# STM32_ESP.net
KiCad netlist of a schematic drawn in Altium Designer
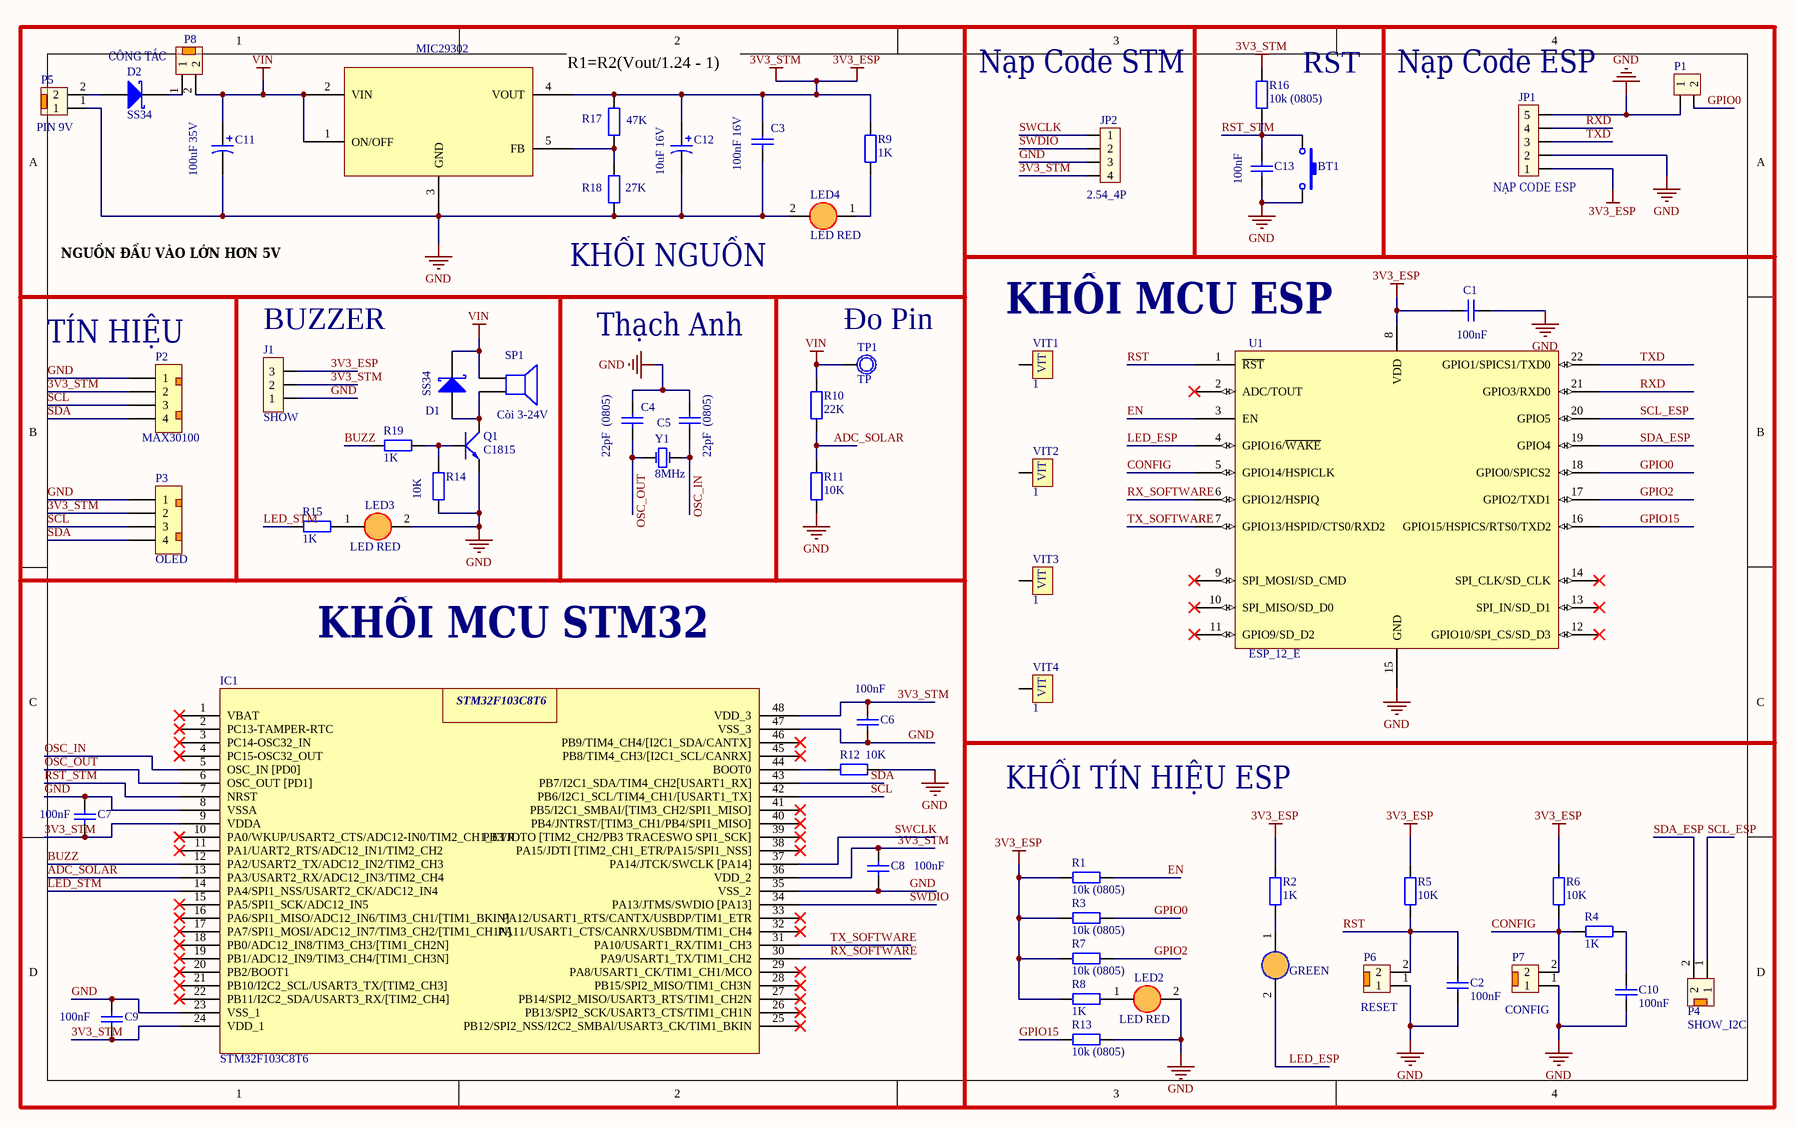
[diagram p0: STM32_ESP.SchDoc]

(export (version "E")
  (design (tool "Eeschema 10.0.6"))
  (components
    (comp (ref "BT1")
      (value "Nút Nhấn 2 Chân 3x6x2.5MM SMD")
      (footprint "Nut Nhan 2 Chan SMD_N")
      (description "Dán")
      (libsource (lib "SCH Chuan") (part "Nut Nhan 2 Chan SMD"))
    )
    (comp (ref "C1")
      (value "100nF")
      (footprint "Tu 0805")
      (description "Dán")
      (libsource (lib "NhomLib") (part "Tu 0805 106 16V 10%"))
    )
    (comp (ref "C2")
      (value "100nF")
      (footprint "tu 0805")
      (description "Dán")
      (libsource (lib "NhomLib") (part "Tu 0805 6.8nF 50V 10%"))
    )
    (comp (ref "C3")
      (value "100nF 16V")
      (footprint "tu 0805")
      (description "Dán")
      (libsource (lib "SCH Chuan") (part "Tu 0805 22pF 50V 10%"))
    )
    (comp (ref "C4")
      (value "22pF  (0805)")
      (footprint "tu 0805")
      (description "Dán")
      (libsource (lib "SCH Chuan") (part "Tu 0805 22pF 50V 10%"))
    )
    (comp (ref "C5")
      (value "22pF  (0805)")
      (footprint "tu 0805")
      (description "Dán")
      (libsource (lib "SCH Chuan") (part "Tu 0805 22pF 50V 10%"))
    )
    (comp (ref "C6")
      (value "100nF")
      (footprint "tu 0805")
      (description "Dán")
      (libsource (lib "SCH Chuan") (part "Tu 0805 104 50V 10%"))
    )
    (comp (ref "C7")
      (value "100nF")
      (footprint "tu 0805")
      (description "Dán")
      (libsource (lib "SCH Chuan") (part "Tu 0805 104 50V 10%"))
    )
    (comp (ref "C8")
      (value "100nF")
      (footprint "tu 0805")
      (description "Dán")
      (libsource (lib "SCH Chuan") (part "Tu 0805 104 50V 10%"))
    )
    (comp (ref "C9")
      (value "100nF")
      (footprint "tu 0805")
      (description "Dán")
      (libsource (lib "SCH Chuan") (part "Tu 0805 104 50V 10%"))
    )
    (comp (ref "C10")
      (value "100nF")
      (footprint "tu 0805")
      (description "Dán")
      (libsource (lib "NhomLib") (part "Tu 0805 6.8nF 50V 10%"))
    )
    (comp (ref "C11")
      (value "100uF 35V")
      (footprint "CAP_ALUM_SMD_100102_TYPE_G")
      (description "CAP ALUM 330uF 20% 35V SMD")
      (fields (field (name "MPN") "EEE-FK1C331P") (field (name "MFR") "Panasonic"))
      (libsource (lib "NhomLib") (part "EEE-FK1C331P"))
    )
    (comp (ref "C12")
      (value "10uF 16V")
      (footprint "CAP_ALUM_SMD_5054_TYPE_C")
      (description "CAP ALUM 33uF 20% 16V SMD")
      (fields (field (name "MPN") "EEE-FK1C330P") (field (name "MFR") "Panasonic"))
      (libsource (lib "NhomLib") (part "EEE-FK1C330P"))
    )
    (comp (ref "C13")
      (value "100nF")
      (footprint "tu 0805")
      (description "Dán")
      (libsource (lib "SCH Chuan") (part "Tu 0805 104 50V 10%"))
    )
    (comp (ref "D1")
      (value "SS34")
      (footprint "DIODE_DO214AC_SMA")
      (description "DIODE SCHOTTKY 40V 3A SMA")
      (libsource (lib "NhomLib") (part "SS34"))
    )
    (comp (ref "D2")
      (value "SS34")
      (footprint "DIODE_DO214AC_SMA")
      (description "DIODE SCHOTTKY 40V 3A SMA")
      (libsource (lib "NhomLib") (part "SS34"))
    )
    (comp (ref "IC1")
      (value "STM32F103C8T6")
      (footprint "LQFP48")
      (description "Dán")
      (libsource (lib "SCH Chuan") (part "STM32F103C8T6"))
    )
    (comp (ref "J1")
      (value "SHOW")
      (footprint "jump don duc thang 2.54_3p")
      (description "Cắm")
      (libsource (lib "NhomLib") (part "Jump Don Duc Thang 2.54_3P"))
    )
    (comp (ref "JP1")
      (value "NẠP CODE ESP")
      (footprint "jump don duc 2.54_5p")
      (description "Cắm")
      (libsource (lib "NhomLib") (part "Jump Don Duc 2.54_5P"))
    )
    (comp (ref "JP2")
      (value "2.54_4P")
      (footprint "JUMP DON DUC 2.54_4P")
      (description "Cắm")
      (libsource (lib "SCH Chuan") (part "Jump Don Duc 2.54_4P"))
    )
    (comp (ref "LED1")
      (value "GREEN")
      (footprint "led 0805")
      (description "Dán")
      (libsource (lib "NhomLib") (part "Led 0805 Xanh Duong"))
    )
    (comp (ref "LED2")
      (value "LED RED")
      (footprint "led 0805")
      (description "Dán")
      (libsource (lib "NhomLib") (part "Led 0805 Do"))
    )
    (comp (ref "LED3")
      (value "LED RED")
      (footprint "led 0805")
      (description "Dán")
      (libsource (lib "NhomLib") (part "Led 0805 Do"))
    )
    (comp (ref "LED4")
      (value "LED RED")
      (footprint "led 0805")
      (description "Dán")
      (libsource (lib "SCH Chuan") (part "Led 0805 Do"))
    )
    (comp (ref "MIC1")
      (value "MIC29302")
      (footprint "Mic5V")
      (description "3A")
      (libsource (lib "node_mcu") (part "Mic5V"))
    )
    (comp (ref "P1")
      (value "2P")
      (footprint "Jump don duc 2.54_2P")
      (description "Cắm")
      (libsource (lib "NhomLib") (part "Jum don duc 2.54_2P"))
    )
    (comp (ref "P2")
      (value "MAX30100")
      (footprint "Header Duc Thang 4p 2.54")
      (description "Cắm")
      (libsource (lib "NhomLib") (part "Header 2.54_4p Duc Thang"))
    )
    (comp (ref "P3")
      (value "OLED")
      (footprint "Header Duc Thang 4p 2.54")
      (description "Cắm")
      (libsource (lib "NhomLib") (part "Header 2.54_4p Duc Thang"))
    )
    (comp (ref "P4")
      (value "SHOW_I2C")
      (footprint "Header Duc Thang 2P 2.54")
      (description "Cắm")
      (libsource (lib "") (part "Header 2.54-2p Duc Thang_2"))
    )
    (comp (ref "P5")
      (value "PIN 9V")
      (footprint "Header Duc Thang 2P 2.54")
      (description "Cắm")
      (libsource (lib "NhomLib") (part "Header 2.54-2p Duc Thang"))
    )
    (comp (ref "P6")
      (value "RESET")
      (footprint "Header Duc Thang 2P 2.54")
      (description "Cắm")
      (libsource (lib "NhomLib") (part "Header 2.54-2p Duc Thang"))
    )
    (comp (ref "P7")
      (value "CONFIG")
      (footprint "Header Duc Thang 2P 2.54")
      (description "Cắm")
      (libsource (lib "NhomLib") (part "Header 2.54-2p Duc Thang"))
    )
    (comp (ref "P8")
      (value "CÔNG TẮC")
      (footprint "Header Duc Thang 2P 2.54")
      (description "Cắm")
      (libsource (lib "") (part "Header 2.54-2p Duc Thang_1"))
    )
    (comp (ref "Q1")
      (value "C1815")
      (footprint "SOT23B")
      (description "Dán")
      (libsource (lib "SCH Chuan") (part "C1815"))
    )
    (comp (ref "R1")
      (value "10k (0805)")
      (footprint "tro 0805")
      (description "Dán")
      (libsource (lib "NhomLib") (part "Tro 0805 5% 10k"))
    )
    (comp (ref "R2")
      (value "1K")
      (footprint "tro 0805")
      (description "Dán")
      (libsource (lib "NhomLib") (part "Tro 0805 5% 1.5k"))
    )
    (comp (ref "R3")
      (value "10k (0805)")
      (footprint "tro 0805")
      (description "Dán")
      (libsource (lib "NhomLib") (part "Tro 0805 5% 10k"))
    )
    (comp (ref "R4")
      (value "1K")
      (footprint "tro 0805")
      (description "Dán")
      (libsource (lib "NhomLib") (part "Tro 0805 5% 1.5k"))
    )
    (comp (ref "R5")
      (value "10K")
      (footprint "tro 0805")
      (description "Dán")
      (libsource (lib "NhomLib") (part "Tro 0805 5% 10k"))
    )
    (comp (ref "R6")
      (value "10K")
      (footprint "tro 0805")
      (description "Dán")
      (libsource (lib "NhomLib") (part "Tro 0805 5% 10k"))
    )
    (comp (ref "R7")
      (value "10k (0805)")
      (footprint "tro 0805")
      (description "Dán")
      (libsource (lib "NhomLib") (part "Tro 0805 5% 10k"))
    )
    (comp (ref "R8")
      (value "1K")
      (footprint "tro 0805")
      (description "Dán")
      (libsource (lib "NhomLib") (part "Tro 0805 5% 1.5k"))
    )
    (comp (ref "R9")
      (value "1K")
      (footprint "tro 0805")
      (description "Dán")
      (libsource (lib "NhomLib") (part "Tro 0805 5% 10k"))
    )
    (comp (ref "R10")
      (value "22K")
      (footprint "tro 0805")
      (description "Dán")
      (libsource (lib "SCH Chuan") (part "Tro 0805 5% 10k"))
    )
    (comp (ref "R11")
      (value "10K")
      (footprint "tro 0805")
      (description "Dán")
      (libsource (lib "SCH Chuan") (part "Tro 0805 5% 10k"))
    )
    (comp (ref "R12")
      (value "10K")
      (footprint "tro 0805")
      (description "Dán")
      (libsource (lib "SCH Chuan") (part "Tro 0805 1% 10k"))
    )
    (comp (ref "R13")
      (value "10k (0805)")
      (footprint "tro 0805")
      (description "Dán")
      (libsource (lib "NhomLib") (part "Tro 0805 5% 10k"))
    )
    (comp (ref "R14")
      (value "10K")
      (footprint "tro 0805")
      (description "Dán")
      (libsource (lib "SCH Chuan") (part "Tro 0805 5% 470R"))
    )
    (comp (ref "R15")
      (value "1K")
      (footprint "tro 0805")
      (description "Dán")
      (libsource (lib "NhomLib") (part "Tro 0805 5% 1.5k"))
    )
    (comp (ref "R16")
      (value "10k (0805)")
      (footprint "tro 0805")
      (description "Dán")
      (libsource (lib "SCH Chuan") (part "Tro 0805 5% 10k"))
    )
    (comp (ref "R17")
      (value "47K")
      (footprint "tro 0805")
      (description "Dán")
      (libsource (lib "NhomLib") (part "Tro 0805 5% 10k"))
    )
    (comp (ref "R18")
      (value "27K")
      (footprint "tro 0805")
      (description "Dán")
      (libsource (lib "NhomLib") (part "Tro 0805 5% 10k"))
    )
    (comp (ref "R19")
      (value "1K")
      (footprint "tro 0805")
      (description "Dán")
      (libsource (lib "SCH Chuan") (part "Tro 0805 5% 470R"))
    )
    (comp (ref "SP1")
      (value "Còi 3-24V")
      (footprint "SPEAKER")
      (description "Cắm")
      (libsource (lib "NhomLib") (part "Coi Chip 5V"))
    )
    (comp (ref "TP1")
      (value "TP")
      (footprint "TP1")
      (description "Test Point")
      (libsource (lib "NhomLib") (part "TP1"))
    )
    (comp (ref "U1")
      (value "ESP_12_E")
      (footprint "ESP8266_12_E_L")
      (description "ESP-12 Wi-Fi Module by AI-Thinker")
      (libsource (lib "Schlib1") (part "ESP_12_E"))
    )
    (comp (ref "VIT1")
      (value "1")
      (footprint "VIT")
      (description "Oc Vit")
      (libsource (lib "NhomLib") (part "VIT"))
    )
    (comp (ref "VIT2")
      (value "1")
      (footprint "VIT")
      (description "Oc Vit")
      (libsource (lib "NhomLib") (part "VIT"))
    )
    (comp (ref "VIT3")
      (value "1")
      (footprint "VIT")
      (description "Oc Vit")
      (libsource (lib "NhomLib") (part "VIT"))
    )
    (comp (ref "VIT4")
      (value "1")
      (footprint "VIT")
      (description "Oc Vit")
      (libsource (lib "NhomLib") (part "VIT"))
    )
    (comp (ref "Y1")
      (value "8MHz")
      (footprint "thach anh 49s smd")
      (description "Dán")
      (libsource (lib "SCH Chuan") (part "Thach anh 8MHz 49S SMD"))
    )
  )
  (nets
    (net (code "1") (name "/ADC_SOLAR") (class "Default")
      (node (ref "IC1") (pin "13") (pinfunction "PA3/USART2_RX/ADC12_IN3/TIM2_CH4_13") (pintype "passive"))
      (node (ref "R10") (pin "1") (pinfunction "1_1") (pintype "passive"))
      (node (ref "R11") (pin "2") (pinfunction "2_2") (pintype "passive"))
    )
    (net (code "2") (name "/BUZZ") (class "Default")
      (node (ref "IC1") (pin "12") (pinfunction "PA2/USART2_TX/ADC12_IN2/TIM2_CH3_12") (pintype "passive"))
      (node (ref "R19") (pin "2") (pinfunction "2_2") (pintype "passive"))
    )
    (net (code "3") (name "/CONFIG") (class "Default")
      (node (ref "P7") (pin "2") (pinfunction "2_2") (pintype "passive"))
      (node (ref "R4") (pin "1") (pinfunction "1_1") (pintype "passive"))
      (node (ref "R6") (pin "2") (pinfunction "2_2") (pintype "passive"))
      (node (ref "U1") (pin "5") (pinfunction "GPIO14/HSPICLK_5") (pintype "bidirectional"))
    )
    (net (code "4") (name "/EN") (class "Default")
      (node (ref "R1") (pin "1") (pinfunction "1_1") (pintype "passive"))
      (node (ref "U1") (pin "3") (pinfunction "EN_3") (pintype "passive"))
    )
    (net (code "5") (name "/GPIO0") (class "Default")
      (node (ref "P1") (pin "2") (pinfunction "2_2") (pintype "passive"))
      (node (ref "R3") (pin "1") (pinfunction "1_1") (pintype "passive"))
      (node (ref "U1") (pin "18") (pinfunction "GPIO0/SPICS2_18") (pintype "bidirectional"))
    )
    (net (code "6") (name "/GPIO2") (class "Default")
      (node (ref "R7") (pin "1") (pinfunction "1_1") (pintype "passive"))
      (node (ref "U1") (pin "17") (pinfunction "GPIO2/TXD1_17") (pintype "bidirectional"))
    )
    (net (code "7") (name "/GPIO15") (class "Default")
      (node (ref "R13") (pin "2") (pinfunction "2_2") (pintype "passive"))
      (node (ref "U1") (pin "16") (pinfunction "GPIO15/HSPICS/RTS0/TXD2_16") (pintype "bidirectional"))
    )
    (net (code "8") (name "/LED_ESP") (class "Default")
      (node (ref "LED1") (pin "2") (pinfunction "K_2") (pintype "passive"))
      (node (ref "U1") (pin "4") (pinfunction "GPIO16/~{WAKE}_4") (pintype "bidirectional"))
    )
    (net (code "9") (name "/LED_STM") (class "Default")
      (node (ref "IC1") (pin "14") (pinfunction "PA4/SPI1_NSS/USART2_CK/ADC12_IN4_14") (pintype "passive"))
      (node (ref "R15") (pin "1") (pinfunction "1_1") (pintype "passive"))
    )
    (net (code "10") (name "/OSC_IN") (class "Default")
      (node (ref "C5") (pin "2") (pinfunction "2_2") (pintype "passive"))
      (node (ref "IC1") (pin "5") (pinfunction "OSC_IN_[PD0]_5") (pintype "passive"))
      (node (ref "Y1") (pin "2") (pinfunction "OSC2_2") (pintype "passive"))
    )
    (net (code "11") (name "/OSC_OUT") (class "Default")
      (node (ref "C4") (pin "2") (pinfunction "2_2") (pintype "passive"))
      (node (ref "IC1") (pin "6") (pinfunction "OSC_OUT_[PD1]_6") (pintype "passive"))
      (node (ref "Y1") (pin "1") (pinfunction "OSC1_1") (pintype "passive"))
    )
    (net (code "12") (name "/RST") (class "Default")
      (node (ref "C2") (pin "1") (pinfunction "1_1") (pintype "passive"))
      (node (ref "P6") (pin "2") (pinfunction "2_2") (pintype "passive"))
      (node (ref "R5") (pin "2") (pinfunction "2_2") (pintype "passive"))
      (node (ref "U1") (pin "1") (pinfunction "~{RST}_1") (pintype "passive"))
    )
    (net (code "13") (name "/RST_STM") (class "Default")
      (node (ref "BT1") (pin "1") (pinfunction "1_1") (pintype "passive"))
      (node (ref "C13") (pin "1") (pinfunction "1_1") (pintype "passive"))
      (node (ref "IC1") (pin "7") (pinfunction "NRST_7") (pintype "passive"))
      (node (ref "R16") (pin "1") (pinfunction "1_1") (pintype "passive"))
    )
    (net (code "14") (name "/RXD") (class "Default")
      (node (ref "JP1") (pin "4") (pinfunction "4_4") (pintype "passive"))
      (node (ref "U1") (pin "21") (pinfunction "GPIO3/RXD0_21") (pintype "bidirectional"))
    )
    (net (code "15") (name "/RX_SOFTWARE") (class "Default")
      (node (ref "IC1") (pin "30") (pinfunction "PA9/USART1_TX/TIM1_CH2_30") (pintype "passive"))
      (node (ref "U1") (pin "6") (pinfunction "GPIO12/HSPIQ_6") (pintype "bidirectional"))
    )
    (net (code "16") (name "/SCL") (class "Default")
      (node (ref "IC1") (pin "42") (pinfunction "PB6/I2C1_SCL/TIM4_CH1/[USART1_TX]_42") (pintype "passive"))
      (node (ref "P2") (pin "3") (pinfunction "3_3") (pintype "passive"))
      (node (ref "P3") (pin "3") (pinfunction "3_3") (pintype "passive"))
    )
    (net (code "17") (name "/SCL_ESP") (class "Default")
      (node (ref "P4") (pin "1") (pinfunction "1_1") (pintype "passive"))
      (node (ref "U1") (pin "20") (pinfunction "GPIO5_20") (pintype "bidirectional"))
    )
    (net (code "18") (name "/SDA") (class "Default")
      (node (ref "IC1") (pin "43") (pinfunction "PB7/I2C1_SDA/TIM4_CH2[USART1_RX]_43") (pintype "passive"))
      (node (ref "P2") (pin "4") (pinfunction "4_4") (pintype "passive"))
      (node (ref "P3") (pin "4") (pinfunction "4_4") (pintype "passive"))
    )
    (net (code "19") (name "/SDA_ESP") (class "Default")
      (node (ref "P4") (pin "2") (pinfunction "2_2") (pintype "passive"))
      (node (ref "U1") (pin "19") (pinfunction "GPIO4_19") (pintype "bidirectional"))
    )
    (net (code "20") (name "/SWCLK") (class "Default")
      (node (ref "IC1") (pin "37") (pinfunction "PA14/JTCK/SWCLK_[PA14]_37") (pintype "passive"))
      (node (ref "JP2") (pin "1") (pinfunction "1_1") (pintype "passive"))
    )
    (net (code "21") (name "/SWDIO") (class "Default")
      (node (ref "IC1") (pin "34") (pinfunction "PA13/JTMS/SWDIO_[PA13]_34") (pintype "passive"))
      (node (ref "JP2") (pin "2") (pinfunction "2_2") (pintype "passive"))
    )
    (net (code "22") (name "/TXD") (class "Default")
      (node (ref "JP1") (pin "3") (pinfunction "3_3") (pintype "passive"))
      (node (ref "U1") (pin "22") (pinfunction "GPIO1/SPICS1/TXD0_22") (pintype "bidirectional"))
    )
    (net (code "23") (name "/TX_SOFTWARE") (class "Default")
      (node (ref "IC1") (pin "31") (pinfunction "PA10/USART1_RX/TIM1_CH3_31") (pintype "passive"))
      (node (ref "U1") (pin "7") (pinfunction "GPIO13/HSPID/CTS0/RXD2_7") (pintype "bidirectional"))
    )
    (net (code "24") (name "3V3_ESP") (class "Default")
      (node (ref "C1") (pin "2") (pinfunction "2_2") (pintype "passive"))
      (node (ref "C12") (pin "1") (pinfunction "1_1") (pintype "passive"))
      (node (ref "C3") (pin "1") (pinfunction "1_1") (pintype "passive"))
      (node (ref "C6") (pin "1") (pinfunction "1_1") (pintype "passive"))
      (node (ref "C7") (pin "2") (pinfunction "2_2") (pintype "passive"))
      (node (ref "C8") (pin "1") (pinfunction "1_1") (pintype "passive"))
      (node (ref "C9") (pin "2") (pinfunction "2_2") (pintype "passive"))
      (node (ref "IC1") (pin "24") (pinfunction "VDD_1_24") (pintype "passive"))
      (node (ref "IC1") (pin "36") (pinfunction "VDD_2_36") (pintype "passive"))
      (node (ref "IC1") (pin "48") (pinfunction "VDD_3_48") (pintype "passive"))
      (node (ref "IC1") (pin "9") (pinfunction "VDDA_9") (pintype "passive"))
      (node (ref "J1") (pin "2") (pinfunction "2_2") (pintype "passive"))
      (node (ref "J1") (pin "3") (pinfunction "3_3") (pintype "passive"))
      (node (ref "JP1") (pin "1") (pinfunction "1_1") (pintype "passive"))
      (node (ref "JP2") (pin "4") (pinfunction "4_4") (pintype "passive"))
      (node (ref "MIC1") (pin "4") (pinfunction "VOUT_4") (pintype "passive"))
      (node (ref "P2") (pin "2") (pinfunction "2_2") (pintype "passive"))
      (node (ref "P3") (pin "2") (pinfunction "2_2") (pintype "passive"))
      (node (ref "R1") (pin "2") (pinfunction "2_2") (pintype "passive"))
      (node (ref "R16") (pin "2") (pinfunction "2_2") (pintype "passive"))
      (node (ref "R17") (pin "1") (pinfunction "1_1") (pintype "passive"))
      (node (ref "R2") (pin "1") (pinfunction "1_1") (pintype "passive"))
      (node (ref "R3") (pin "2") (pinfunction "2_2") (pintype "passive"))
      (node (ref "R5") (pin "1") (pinfunction "1_1") (pintype "passive"))
      (node (ref "R6") (pin "1") (pinfunction "1_1") (pintype "passive"))
      (node (ref "R7") (pin "2") (pinfunction "2_2") (pintype "passive"))
      (node (ref "R8") (pin "1") (pinfunction "1_1") (pintype "passive"))
      (node (ref "R9") (pin "2") (pinfunction "2_2") (pintype "passive"))
      (node (ref "U1") (pin "8") (pinfunction "VDD_8") (pintype "power_in"))
    )
    (net (code "25") (name "GND") (class "Default")
      (node (ref "BT1") (pin "2") (pinfunction "2_2") (pintype "passive"))
      (node (ref "C1") (pin "1") (pinfunction "1_1") (pintype "passive"))
      (node (ref "C10") (pin "2") (pinfunction "2_2") (pintype "passive"))
      (node (ref "C11") (pin "2") (pinfunction "2_2") (pintype "passive"))
      (node (ref "C12") (pin "2") (pinfunction "2_2") (pintype "passive"))
      (node (ref "C13") (pin "2") (pinfunction "2_2") (pintype "passive"))
      (node (ref "C2") (pin "2") (pinfunction "2_2") (pintype "passive"))
      (node (ref "C3") (pin "2") (pinfunction "2_2") (pintype "passive"))
      (node (ref "C4") (pin "1") (pinfunction "1_1") (pintype "passive"))
      (node (ref "C5") (pin "1") (pinfunction "1_1") (pintype "passive"))
      (node (ref "C6") (pin "2") (pinfunction "2_2") (pintype "passive"))
      (node (ref "C7") (pin "1") (pinfunction "1_1") (pintype "passive"))
      (node (ref "C8") (pin "2") (pinfunction "2_2") (pintype "passive"))
      (node (ref "C9") (pin "1") (pinfunction "1_1") (pintype "passive"))
      (node (ref "IC1") (pin "23") (pinfunction "VSS_1_23") (pintype "passive"))
      (node (ref "IC1") (pin "35") (pinfunction "VSS_2_35") (pintype "passive"))
      (node (ref "IC1") (pin "47") (pinfunction "VSS_3_47") (pintype "passive"))
      (node (ref "IC1") (pin "8") (pinfunction "VSSA_8") (pintype "passive"))
      (node (ref "J1") (pin "1") (pinfunction "1_1") (pintype "passive"))
      (node (ref "JP1") (pin "2") (pinfunction "2_2") (pintype "passive"))
      (node (ref "JP1") (pin "5") (pinfunction "5_5") (pintype "passive"))
      (node (ref "JP2") (pin "3") (pinfunction "3_3") (pintype "passive"))
      (node (ref "LED2") (pin "2") (pinfunction "K_2") (pintype "passive"))
      (node (ref "LED3") (pin "2") (pinfunction "K_2") (pintype "passive"))
      (node (ref "LED4") (pin "2") (pinfunction "K_2") (pintype "passive"))
      (node (ref "MIC1") (pin "3") (pinfunction "GND_3") (pintype "passive"))
      (node (ref "P1") (pin "1") (pinfunction "1_1") (pintype "passive"))
      (node (ref "P2") (pin "1") (pinfunction "1_1") (pintype "passive"))
      (node (ref "P3") (pin "1") (pinfunction "1_1") (pintype "passive"))
      (node (ref "P5") (pin "1") (pinfunction "1_1") (pintype "passive"))
      (node (ref "P6") (pin "1") (pinfunction "1_1") (pintype "passive"))
      (node (ref "P7") (pin "1") (pinfunction "1_1") (pintype "passive"))
      (node (ref "Q1") (pin "1") (pinfunction "E_1") (pintype "passive"))
      (node (ref "R11") (pin "1") (pinfunction "1_1") (pintype "passive"))
      (node (ref "R12") (pin "2") (pinfunction "2_2") (pintype "passive"))
      (node (ref "R13") (pin "1") (pinfunction "1_1") (pintype "passive"))
      (node (ref "R14") (pin "1") (pinfunction "1_1") (pintype "passive"))
      (node (ref "R18") (pin "2") (pinfunction "2_2") (pintype "passive"))
      (node (ref "U1") (pin "15") (pinfunction "GND_15") (pintype "power_in"))
    )
    (net (code "26") (name "Net-(C10-Pad1)") (class "Default")
      (node (ref "C10") (pin "1") (pinfunction "1_1") (pintype "passive"))
      (node (ref "R4") (pin "2") (pinfunction "2_2") (pintype "passive"))
    )
    (net (code "27") (name "Net-(D1-A)") (class "Default")
      (node (ref "D1") (pin "1") (pinfunction "A_1") (pintype "passive"))
      (node (ref "Q1") (pin "2") (pinfunction "C_2") (pintype "passive"))
      (node (ref "SP1") (pin "2") (pinfunction "2_2") (pintype "passive"))
    )
    (net (code "28") (name "Net-(D2-A)") (class "Default")
      (node (ref "D2") (pin "1") (pinfunction "A_1") (pintype "passive"))
      (node (ref "P5") (pin "2") (pinfunction "2_2") (pintype "passive"))
    )
    (net (code "29") (name "Net-(D2-K)") (class "Default")
      (node (ref "D2") (pin "2") (pinfunction "K_2") (pintype "passive"))
      (node (ref "P8") (pin "1") (pinfunction "1_1") (pintype "passive"))
    )
    (net (code "30") (name "Net-(IC1-BOOT0)") (class "Default")
      (node (ref "IC1") (pin "44") (pinfunction "BOOT0_44") (pintype "passive"))
      (node (ref "R12") (pin "1") (pinfunction "1_1") (pintype "passive"))
    )
    (net (code "31") (name "Net-(LED1-A)") (class "Default")
      (node (ref "LED1") (pin "1") (pinfunction "A_1") (pintype "passive"))
      (node (ref "R2") (pin "2") (pinfunction "2_2") (pintype "passive"))
    )
    (net (code "32") (name "Net-(LED2-A)") (class "Default")
      (node (ref "LED2") (pin "1") (pinfunction "A_1") (pintype "passive"))
      (node (ref "R8") (pin "2") (pinfunction "2_2") (pintype "passive"))
    )
    (net (code "33") (name "Net-(LED3-A)") (class "Default")
      (node (ref "LED3") (pin "1") (pinfunction "A_1") (pintype "passive"))
      (node (ref "R15") (pin "2") (pinfunction "2_2") (pintype "passive"))
    )
    (net (code "34") (name "Net-(LED4-A)") (class "Default")
      (node (ref "LED4") (pin "1") (pinfunction "A_1") (pintype "passive"))
      (node (ref "R9") (pin "1") (pinfunction "1_1") (pintype "passive"))
    )
    (net (code "35") (name "Net-(MIC1-FB)") (class "Default")
      (node (ref "MIC1") (pin "5") (pinfunction "FB_5") (pintype "passive"))
      (node (ref "R17") (pin "2") (pinfunction "2_2") (pintype "passive"))
      (node (ref "R18") (pin "1") (pinfunction "1_1") (pintype "passive"))
    )
    (net (code "36") (name "Net-(Q1-B)") (class "Default")
      (node (ref "Q1") (pin "3") (pinfunction "B_3") (pintype "passive"))
      (node (ref "R14") (pin "2") (pinfunction "2_2") (pintype "passive"))
      (node (ref "R19") (pin "1") (pinfunction "1_1") (pintype "passive"))
    )
    (net (code "37") (name "VIN") (class "Default")
      (node (ref "C11") (pin "1") (pinfunction "1_1") (pintype "passive"))
      (node (ref "D1") (pin "2") (pinfunction "K_2") (pintype "passive"))
      (node (ref "MIC1") (pin "1") (pinfunction "ON/OFF_1") (pintype "passive"))
      (node (ref "MIC1") (pin "2") (pinfunction "VIN_2") (pintype "passive"))
      (node (ref "P8") (pin "2") (pinfunction "2_2") (pintype "passive"))
      (node (ref "R10") (pin "2") (pinfunction "2_2") (pintype "passive"))
      (node (ref "SP1") (pin "1") (pinfunction "1_1") (pintype "passive"))
      (node (ref "TP1") (pin "1") (pinfunction "1_1") (pintype "passive"))
    )
    (net (code "38") (name "unconnected-(IC1-PA0{slash}WKUP{slash}USART2_CTS{slash}ADC12-IN0{slash}TIM2_CH1_ETR-Pad10)") (class "Default")
      (node (ref "IC1") (pin "10") (pinfunction "PA0/WKUP/USART2_CTS/ADC12-IN0/TIM2_CH1_ETR_10") (pintype "passive+no_connect"))
    )
    (net (code "39") (name "unconnected-(IC1-PA1{slash}UART2_RTS{slash}ADC12_IN1{slash}TIM2_CH2-Pad11)") (class "Default")
      (node (ref "IC1") (pin "11") (pinfunction "PA1/UART2_RTS/ADC12_IN1/TIM2_CH2_11") (pintype "passive+no_connect"))
    )
    (net (code "40") (name "unconnected-(IC1-PA5{slash}SPI1_SCK{slash}ADC12_IN5-Pad15)") (class "Default")
      (node (ref "IC1") (pin "15") (pinfunction "PA5/SPI1_SCK/ADC12_IN5_15") (pintype "passive+no_connect"))
    )
    (net (code "41") (name "unconnected-(IC1-PA6{slash}SPI1_MISO{slash}ADC12_IN6{slash}TIM3_CH1{slash}[TIM1_BKIN]-Pad16)") (class "Default")
      (node (ref "IC1") (pin "16") (pinfunction "PA6/SPI1_MISO/ADC12_IN6/TIM3_CH1/[TIM1_BKIN]_16") (pintype "passive+no_connect"))
    )
    (net (code "42") (name "unconnected-(IC1-PA7{slash}SPI1_MOSI{slash}ADC12_IN7{slash}TIM3_CH2{slash}[TIM1_CH1N]-Pad17)") (class "Default")
      (node (ref "IC1") (pin "17") (pinfunction "PA7/SPI1_MOSI/ADC12_IN7/TIM3_CH2/[TIM1_CH1N]_17") (pintype "passive+no_connect"))
    )
    (net (code "43") (name "unconnected-(IC1-PA8{slash}USART1_CK{slash}TIM1_CH1{slash}MCO-Pad29)") (class "Default")
      (node (ref "IC1") (pin "29") (pinfunction "PA8/USART1_CK/TIM1_CH1/MCO_29") (pintype "passive+no_connect"))
    )
    (net (code "44") (name "unconnected-(IC1-PA11{slash}USART1_CTS{slash}CANRX{slash}USBDM{slash}TIM1_CH4-Pad32)") (class "Default")
      (node (ref "IC1") (pin "32") (pinfunction "PA11/USART1_CTS/CANRX/USBDM/TIM1_CH4_32") (pintype "passive+no_connect"))
    )
    (net (code "45") (name "unconnected-(IC1-PA12{slash}USART1_RTS{slash}CANTX{slash}USBDP{slash}TIM1_ETR-Pad33)") (class "Default")
      (node (ref "IC1") (pin "33") (pinfunction "PA12/USART1_RTS/CANTX/USBDP/TIM1_ETR_33") (pintype "passive+no_connect"))
    )
    (net (code "46") (name "unconnected-(IC1-PA15{slash}JDTI_[TIM2_CH1_ETR{slash}PA15{slash}SPI1_NSS]-Pad38)") (class "Default")
      (node (ref "IC1") (pin "38") (pinfunction "PA15/JDTI_[TIM2_CH1_ETR/PA15/SPI1_NSS]_38") (pintype "passive+no_connect"))
    )
    (net (code "47") (name "unconnected-(IC1-PB0{slash}ADC12_IN8{slash}TIM3_CH3{slash}[TIM1_CH2N]-Pad18)") (class "Default")
      (node (ref "IC1") (pin "18") (pinfunction "PB0/ADC12_IN8/TIM3_CH3/[TIM1_CH2N]_18") (pintype "passive+no_connect"))
    )
    (net (code "48") (name "unconnected-(IC1-PB1{slash}ADC12_IN9{slash}TIM3_CH4{slash}[TIM1_CH3N]-Pad19)") (class "Default")
      (node (ref "IC1") (pin "19") (pinfunction "PB1/ADC12_IN9/TIM3_CH4/[TIM1_CH3N]_19") (pintype "passive+no_connect"))
    )
    (net (code "49") (name "unconnected-(IC1-PB2{slash}BOOT1-Pad20)") (class "Default")
      (node (ref "IC1") (pin "20") (pinfunction "PB2/BOOT1_20") (pintype "passive+no_connect"))
    )
    (net (code "50") (name "unconnected-(IC1-PB3{slash}JDTO_[TIM2_CH2{slash}PB3_TRACESWO_SPI1_SCK]-Pad39)") (class "Default")
      (node (ref "IC1") (pin "39") (pinfunction "PB3/JDTO_[TIM2_CH2/PB3_TRACESWO_SPI1_SCK]_39") (pintype "passive+no_connect"))
    )
    (net (code "51") (name "unconnected-(IC1-PB4{slash}JNTRST{slash}[TIM3_CH1{slash}PB4{slash}SPI1_MISO]-Pad40)") (class "Default")
      (node (ref "IC1") (pin "40") (pinfunction "PB4/JNTRST/[TIM3_CH1/PB4/SPI1_MISO]_40") (pintype "passive+no_connect"))
    )
    (net (code "52") (name "unconnected-(IC1-PB5{slash}I2C1_SMBAI{slash}[TIM3_CH2{slash}SPI1_MISO]-Pad41)") (class "Default")
      (node (ref "IC1") (pin "41") (pinfunction "PB5/I2C1_SMBAI/[TIM3_CH2/SPI1_MISO]_41") (pintype "passive+no_connect"))
    )
    (net (code "53") (name "unconnected-(IC1-PB8{slash}TIM4_CH3{slash}[I2C1_SCL{slash}CANRX]-Pad45)") (class "Default")
      (node (ref "IC1") (pin "45") (pinfunction "PB8/TIM4_CH3/[I2C1_SCL/CANRX]_45") (pintype "passive+no_connect"))
    )
    (net (code "54") (name "unconnected-(IC1-PB9{slash}TIM4_CH4{slash}[I2C1_SDA{slash}CANTX]-Pad46)") (class "Default")
      (node (ref "IC1") (pin "46") (pinfunction "PB9/TIM4_CH4/[I2C1_SDA/CANTX]_46") (pintype "passive+no_connect"))
    )
    (net (code "55") (name "unconnected-(IC1-PB10{slash}I2C2_SCL{slash}USART3_TX{slash}[TIM2_CH3]-Pad21)") (class "Default")
      (node (ref "IC1") (pin "21") (pinfunction "PB10/I2C2_SCL/USART3_TX/[TIM2_CH3]_21") (pintype "passive+no_connect"))
    )
    (net (code "56") (name "unconnected-(IC1-PB11{slash}I2C2_SDA{slash}USART3_RX{slash}[TIM2_CH4]-Pad22)") (class "Default")
      (node (ref "IC1") (pin "22") (pinfunction "PB11/I2C2_SDA/USART3_RX/[TIM2_CH4]_22") (pintype "passive+no_connect"))
    )
    (net (code "57") (name "unconnected-(IC1-PB12{slash}SPI2_NSS{slash}I2C2_SMBAl{slash}USART3_CK{slash}TIM1_BKIN-Pad25)") (class "Default")
      (node (ref "IC1") (pin "25") (pinfunction "PB12/SPI2_NSS/I2C2_SMBAl/USART3_CK/TIM1_BKIN_25") (pintype "passive+no_connect"))
    )
    (net (code "58") (name "unconnected-(IC1-PB13{slash}SPI2_SCK{slash}USART3_CTS{slash}TIM1_CH1N-Pad26)") (class "Default")
      (node (ref "IC1") (pin "26") (pinfunction "PB13/SPI2_SCK/USART3_CTS/TIM1_CH1N_26") (pintype "passive+no_connect"))
    )
    (net (code "59") (name "unconnected-(IC1-PB14{slash}SPI2_MISO{slash}USART3_RTS{slash}TIM1_CH2N-Pad27)") (class "Default")
      (node (ref "IC1") (pin "27") (pinfunction "PB14/SPI2_MISO/USART3_RTS/TIM1_CH2N_27") (pintype "passive+no_connect"))
    )
    (net (code "60") (name "unconnected-(IC1-PB15{slash}SPI2_MISO{slash}TIM1_CH3N-Pad28)") (class "Default")
      (node (ref "IC1") (pin "28") (pinfunction "PB15/SPI2_MISO/TIM1_CH3N_28") (pintype "passive+no_connect"))
    )
    (net (code "61") (name "unconnected-(IC1-PC13-TAMPER-RTC-Pad2)") (class "Default")
      (node (ref "IC1") (pin "2") (pinfunction "PC13-TAMPER-RTC_2") (pintype "passive+no_connect"))
    )
    (net (code "62") (name "unconnected-(IC1-PC14-OSC32_IN-Pad3)") (class "Default")
      (node (ref "IC1") (pin "3") (pinfunction "PC14-OSC32_IN_3") (pintype "passive+no_connect"))
    )
    (net (code "63") (name "unconnected-(IC1-PC15-OSC32_OUT-Pad4)") (class "Default")
      (node (ref "IC1") (pin "4") (pinfunction "PC15-OSC32_OUT_4") (pintype "passive+no_connect"))
    )
    (net (code "64") (name "unconnected-(IC1-VBAT-Pad1)") (class "Default")
      (node (ref "IC1") (pin "1") (pinfunction "VBAT_1") (pintype "passive+no_connect"))
    )
    (net (code "65") (name "unconnected-(U1-ADC{slash}TOUT-Pad2)") (class "Default")
      (node (ref "U1") (pin "2") (pinfunction "ADC/TOUT_2") (pintype "bidirectional+no_connect"))
    )
    (net (code "66") (name "unconnected-(U1-GPIO9{slash}SD_D2-Pad11)") (class "Default")
      (node (ref "U1") (pin "11") (pinfunction "GPIO9/SD_D2_11") (pintype "bidirectional+no_connect"))
    )
    (net (code "67") (name "unconnected-(U1-GPIO10{slash}SPI_CS{slash}SD_D3-Pad12)") (class "Default")
      (node (ref "U1") (pin "12") (pinfunction "GPIO10/SPI_CS/SD_D3_12") (pintype "bidirectional+no_connect"))
    )
    (net (code "68") (name "unconnected-(U1-SPI_CLK{slash}SD_CLK-Pad14)") (class "Default")
      (node (ref "U1") (pin "14") (pinfunction "SPI_CLK/SD_CLK_14") (pintype "bidirectional+no_connect"))
    )
    (net (code "69") (name "unconnected-(U1-SPI_IN{slash}SD_D1-Pad13)") (class "Default")
      (node (ref "U1") (pin "13") (pinfunction "SPI_IN/SD_D1_13") (pintype "bidirectional+no_connect"))
    )
    (net (code "70") (name "unconnected-(U1-SPI_MISO{slash}SD_D0-Pad10)") (class "Default")
      (node (ref "U1") (pin "10") (pinfunction "SPI_MISO/SD_D0_10") (pintype "bidirectional+no_connect"))
    )
    (net (code "71") (name "unconnected-(U1-SPI_MOSI{slash}SD_CMD-Pad9)") (class "Default")
      (node (ref "U1") (pin "9") (pinfunction "SPI_MOSI/SD_CMD_9") (pintype "bidirectional+no_connect"))
    )
    (net (code "72") (name "unconnected-(VIT1-1-PadVIT1)") (class "Default")
      (node (ref "VIT1") (pin "VIT1") (pinfunction "1_VIT1") (pintype "passive"))
    )
    (net (code "73") (name "unconnected-(VIT2-1-PadVIT1)") (class "Default")
      (node (ref "VIT2") (pin "VIT1") (pinfunction "1_VIT1") (pintype "passive"))
    )
    (net (code "74") (name "unconnected-(VIT3-1-PadVIT1)") (class "Default")
      (node (ref "VIT3") (pin "VIT1") (pinfunction "1_VIT1") (pintype "passive"))
    )
    (net (code "75") (name "unconnected-(VIT4-1-PadVIT1)") (class "Default")
      (node (ref "VIT4") (pin "VIT1") (pinfunction "1_VIT1") (pintype "passive"))
    )
  )
)
